# GSM_Module.net
KiCad netlist of a schematic drawn in Altium Designer
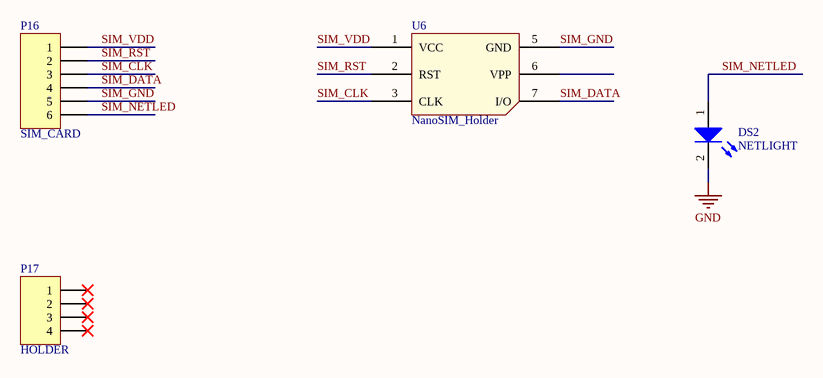
[diagram p0: GSM_Module.SchDoc]

(export (version "E")
  (design (tool "Eeschema 10.0.6"))
  (components
    (comp (ref "DS2")
      (value "NETLIGHT")
      (footprint "0805_LED")
      (description "LED 5mm Diameter")
      (fields (field (name "PUBLISHER") "Altium Limited"))
      (libsource (lib "Miscellaneous Devices") (part "LED0"))
    )
    (comp (ref "P16")
      (value "SIM_CARD")
      (footprint "HDR1X6")
      (description "Header, 6-Pin")
      (fields (field (name "PUBLISHER") "Altium Limited"))
      (libsource (lib "Miscellaneous Connectors") (part "Header 6"))
    )
    (comp (ref "P17")
      (value "HOLDER")
      (footprint "HDR1X4")
      (description "Header, 4-Pin")
      (fields (field (name "PUBLISHER") "Altium Limited"))
      (libsource (lib "Miscellaneous Connectors") (part "Header 4"))
    )
    (comp (ref "U6")
      (value "NanoSIM_Holder")
      (footprint "Nano_SIMCard_Holder")
      (libsource (lib "SchLib") (part "NanoSIM_Holder"))
    )
  )
  (nets
    (net (code "1") (name "/SIM_CLK") (class "Default")
      (node (ref "P16") (pin "3") (pinfunction "3_3") (pintype "passive"))
      (node (ref "U6") (pin "3") (pinfunction "CLK_3") (pintype "passive"))
    )
    (net (code "2") (name "/SIM_DATA") (class "Default")
      (node (ref "P16") (pin "4") (pinfunction "4_4") (pintype "passive"))
      (node (ref "U6") (pin "7") (pinfunction "I/O_7") (pintype "passive"))
    )
    (net (code "3") (name "/SIM_GND") (class "Default")
      (node (ref "P16") (pin "5") (pinfunction "5_5") (pintype "passive"))
      (node (ref "U6") (pin "5") (pinfunction "GND_5") (pintype "passive"))
    )
    (net (code "4") (name "/SIM_NETLED") (class "Default")
      (node (ref "DS2") (pin "1") (pinfunction "A_1") (pintype "passive"))
      (node (ref "P16") (pin "6") (pinfunction "6_6") (pintype "passive"))
    )
    (net (code "5") (name "/SIM_RST") (class "Default")
      (node (ref "P16") (pin "2") (pinfunction "2_2") (pintype "passive"))
      (node (ref "U6") (pin "2") (pinfunction "RST_2") (pintype "passive"))
    )
    (net (code "6") (name "/SIM_VDD") (class "Default")
      (node (ref "P16") (pin "1") (pinfunction "1_1") (pintype "passive"))
      (node (ref "U6") (pin "1") (pinfunction "VCC_1") (pintype "passive"))
    )
    (net (code "7") (name "GND") (class "Default")
      (node (ref "DS2") (pin "2") (pinfunction "K_2") (pintype "passive"))
    )
    (net (code "8") (name "unconnected-(P17-Pad1)") (class "Default")
      (node (ref "P17") (pin "1") (pinfunction "1_1") (pintype "passive+no_connect"))
    )
    (net (code "9") (name "unconnected-(P17-Pad2)") (class "Default")
      (node (ref "P17") (pin "2") (pinfunction "2_2") (pintype "passive+no_connect"))
    )
    (net (code "10") (name "unconnected-(P17-Pad3)") (class "Default")
      (node (ref "P17") (pin "3") (pinfunction "3_3") (pintype "passive+no_connect"))
    )
    (net (code "11") (name "unconnected-(P17-Pad4)") (class "Default")
      (node (ref "P17") (pin "4") (pinfunction "4_4") (pintype "passive+no_connect"))
    )
    (net (code "12") (name "unconnected-(U6-VPP-Pad6)") (class "Default")
      (node (ref "U6") (pin "6") (pinfunction "VPP_6") (pintype "passive"))
    )
  )
)
